# Negative_Pwr.net
KiCad netlist of a schematic drawn in Altium Designer
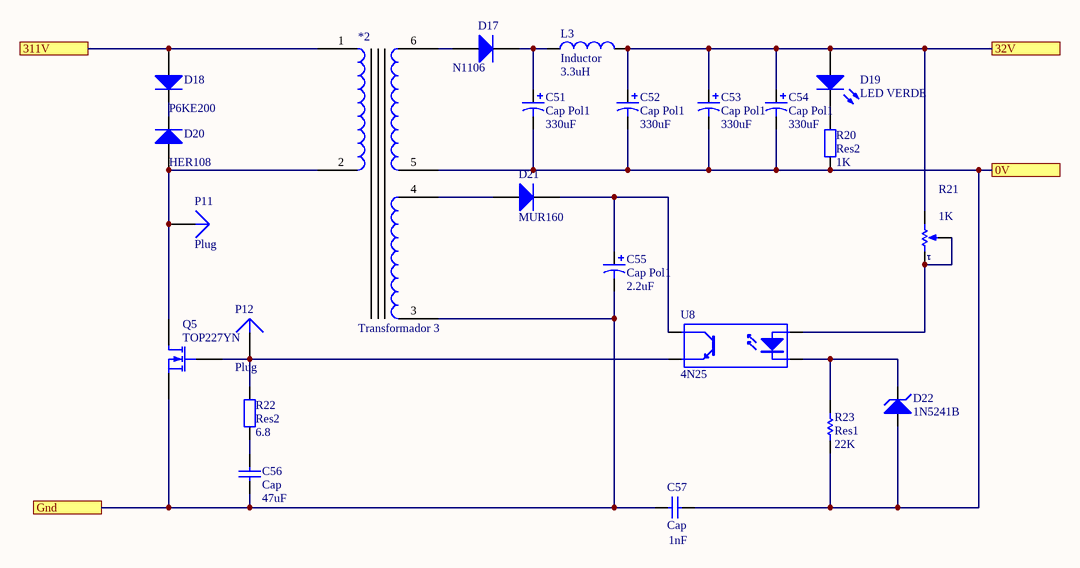
[diagram p0: Negative Pwr.SchDoc]

(export (version "E")
  (design (tool "Eeschema 10.0.6"))
  (components
    (comp (ref "*2")
      (value "Transformador 3")
      (footprint "Transformador_flyback - duplicate")
      (libsource (lib "Userlib") (part "Transformador 3"))
    )
    (comp (ref "C51")
      (value "Cap Pol1")
      (footprint "CAPR D500 H1200 R200 mil")
      (description "Polarized Capacitor (Radial)")
      (fields (field (name "ALTIUM_VALUE") "330uF") (field (name "PUBLISHER") "Altium Limited"))
      (libsource (lib "Miscellaneous Devices") (part "Cap Pol1"))
    )
    (comp (ref "C52")
      (value "Cap Pol1")
      (footprint "CAPR D500 H1200 R200 mil")
      (description "Polarized Capacitor (Radial)")
      (fields (field (name "ALTIUM_VALUE") "330uF") (field (name "PUBLISHER") "Altium Limited"))
      (libsource (lib "Miscellaneous Devices") (part "Cap Pol1"))
    )
    (comp (ref "C53")
      (value "Cap Pol1")
      (footprint "CAPR D500 H1200 R200 mil")
      (description "Polarized Capacitor (Radial)")
      (fields (field (name "ALTIUM_VALUE") "330uF") (field (name "PUBLISHER") "Altium Limited"))
      (libsource (lib "Miscellaneous Devices") (part "Cap Pol1"))
    )
    (comp (ref "C54")
      (value "Cap Pol1")
      (footprint "CAPR D500 H1200 R200 mil")
      (description "Polarized Capacitor (Radial)")
      (fields (field (name "ALTIUM_VALUE") "330uF") (field (name "PUBLISHER") "Altium Limited"))
      (libsource (lib "Miscellaneous Devices") (part "Cap Pol1"))
    )
    (comp (ref "C55")
      (value "Cap Pol1")
      (footprint "CAPR D200 H450 R100 mil")
      (description "Polarized Capacitor (Radial)")
      (fields (field (name "ALTIUM_VALUE") "2.2uF") (field (name "PUBLISHER") "Altium Limited"))
      (libsource (lib "Miscellaneous Devices") (part "Cap Pol1"))
    )
    (comp (ref "C56")
      (value "Cap")
      (footprint "CAPR D250 H450 R100 mil")
      (description "Capacitor")
      (fields (field (name "ALTIUM_VALUE") "47uF") (field (name "PUBLISHER") "Altium Limited"))
      (libsource (lib "Miscellaneous Devices") (part "Cap"))
    )
    (comp (ref "C57")
      (value "Cap")
      (footprint "RAD-0.2")
      (description "Capacitor")
      (fields (field (name "ALTIUM_VALUE") "1nF") (field (name "PUBLISHER") "Altium Limited"))
      (libsource (lib "Miscellaneous Devices") (part "Cap"))
    )
    (comp (ref "D17")
      (value "N1106")
      (footprint "TO-220_A")
      (description "High Conductance Fast Diode")
      (fields (field (name "PUBLISHER") "Altium Limited"))
      (libsource (lib "") (part "Diode 1N4148_1"))
    )
    (comp (ref "D18")
      (value "P6KE200")
      (footprint "DO-15")
      (description "High Conductance Fast Diode")
      (fields (field (name "PUBLISHER") "Altium Limited"))
      (libsource (lib "Miscellaneous Devices") (part "Diode 1N4148"))
    )
    (comp (ref "D19")
      (value "LED VERDE")
      (footprint "Led 5mm ROJO")
      (description "Typical INFRARED GaAs LED")
      (fields (field (name "PUBLISHER") "Altium Limited"))
      (libsource (lib "Miscellaneous Devices") (part "LED0"))
    )
    (comp (ref "D20")
      (value "HER108")
      (footprint "DO-41")
      (description "High Conductance Fast Diode")
      (fields (field (name "PUBLISHER") "Altium Limited"))
      (libsource (lib "Miscellaneous Devices") (part "Diode 1N4148"))
    )
    (comp (ref "D21")
      (value "MUR160")
      (footprint "DO-41")
      (description "High Conductance Fast Diode")
      (fields (field (name "PUBLISHER") "Altium Limited"))
      (libsource (lib "Miscellaneous Devices") (part "Diode 1N4148"))
    )
    (comp (ref "D22")
      (value "Diodo Zener")
      (footprint "DO-41")
      (fields (field (name "VALOR") "1N5241B"))
      (libsource (lib "RUF-Dispositivos-Grales") (part "Diodo Zener"))
    )
    (comp (ref "L3")
      (value "Inductor")
      (footprint "Bobina 1.5*3")
      (fields (field (name "ALTIUM_VALUE") "3.3uH") (field (name "PUBLISHER") "Altium Limited"))
      (libsource (lib "Miscellaneous Devices") (part "Inductor"))
    )
    (comp (ref "P11")
      (value "Plug")
      (footprint "PIN1")
      (fields (field (name "PUBLISHER") "Altium Limited"))
      (libsource (lib "Miscellaneous Connectors") (part "Plug"))
    )
    (comp (ref "P12")
      (value "Plug")
      (footprint "PIN1")
      (fields (field (name "PUBLISHER") "Altium Limited"))
      (libsource (lib "Miscellaneous Connectors") (part "Plug"))
    )
    (comp (ref "Q5")
      (value "TOP227YN")
      (footprint "TO-220AB")
      (description "N-Channel MOSFET")
      (fields (field (name "PUBLISHER") "Altium Limited"))
      (libsource (lib "Miscellaneous Devices") (part "MOSFET-N"))
    )
    (comp (ref "R20")
      (value "Res2")
      (footprint "1206 resistor")
      (description "Resistor")
      (fields (field (name "ALTIUM_VALUE") "1K") (field (name "PUBLISHER") "Altium Limited"))
      (libsource (lib "Miscellaneous Devices") (part "Res2"))
    )
    (comp (ref "R21")
      (value "Trimpot")
      (footprint "Trimpot Horizontal")
      (description "Preset")
      (fields (field (name "VALOR") "1K"))
      (libsource (lib "RUF-Dispositivos-Grales") (part "Trimpot"))
    )
    (comp (ref "R22")
      (value "Res2")
      (footprint "1206 resistor")
      (description "Resistor")
      (fields (field (name "ALTIUM_VALUE") "6.8") (field (name "PUBLISHER") "Altium Limited"))
      (libsource (lib "Miscellaneous Devices") (part "Res2"))
    )
    (comp (ref "R23")
      (value "Res1")
      (footprint "1206 resistor")
      (description "Resistor")
      (fields (field (name "ALTIUM_VALUE") "22K") (field (name "PUBLISHER") "Altium Limited"))
      (libsource (lib "Miscellaneous Devices") (part "Res1"))
    )
    (comp (ref "U8")
      (value "4N25")
      (footprint "DIP-4")
      (description "4-Pin Phototransistor Optocoupler")
      (fields (field (name "PUBLISHER") "Altium Limited"))
      (libsource (lib "Miscellaneous Devices") (part "Optoisolator1"))
    )
  )
  (nets
    (net (code "1") (name "/0V") (class "Default")
      (node (ref "*2") (pin "5") (pinfunction "L_5") (pintype "passive"))
      (node (ref "C51") (pin "2") (pinfunction "2_2") (pintype "passive"))
      (node (ref "C52") (pin "2") (pinfunction "2_2") (pintype "passive"))
      (node (ref "C53") (pin "2") (pinfunction "2_2") (pintype "passive"))
      (node (ref "C54") (pin "2") (pinfunction "2_2") (pintype "passive"))
      (node (ref "C57") (pin "2") (pinfunction "2_2") (pintype "passive"))
      (node (ref "D22") (pin "1") (pinfunction "A_1") (pintype "passive"))
      (node (ref "R20") (pin "1") (pinfunction "1_1") (pintype "passive"))
      (node (ref "R23") (pin "1") (pinfunction "1_1") (pintype "passive"))
    )
    (net (code "2") (name "/32V") (class "Default")
      (node (ref "C52") (pin "1") (pinfunction "1_1") (pintype "passive"))
      (node (ref "C53") (pin "1") (pinfunction "1_1") (pintype "passive"))
      (node (ref "C54") (pin "1") (pinfunction "1_1") (pintype "passive"))
      (node (ref "D19") (pin "1") (pinfunction "A_1") (pintype "passive"))
      (node (ref "L3") (pin "2") (pinfunction "2_2") (pintype "passive"))
      (node (ref "R21") (pin "2") (pinfunction "BOT_2") (pintype "passive"))
    )
    (net (code "3") (name "/311V") (class "Default")
      (node (ref "*2") (pin "1") (pinfunction "L_1") (pintype "passive"))
      (node (ref "D18") (pin "1") (pinfunction "A_1") (pintype "passive"))
    )
    (net (code "4") (name "/Gnd") (class "Default")
      (node (ref "*2") (pin "3") (pinfunction "L_3") (pintype "passive"))
      (node (ref "C55") (pin "2") (pinfunction "2_2") (pintype "passive"))
      (node (ref "C56") (pin "1") (pinfunction "1_1") (pintype "passive"))
      (node (ref "C57") (pin "1") (pinfunction "1_1") (pintype "passive"))
      (node (ref "Q5") (pin "2") (pinfunction "S_2") (pintype "passive"))
    )
    (net (code "5") (name "Net-(C56-Pad2)") (class "Default")
      (node (ref "C56") (pin "2") (pinfunction "2_2") (pintype "passive"))
      (node (ref "R22") (pin "1") (pinfunction "1_1") (pintype "passive"))
    )
    (net (code "6") (name "Net-(D17-A)") (class "Default")
      (node (ref "*2") (pin "6") (pinfunction "L_6") (pintype "passive"))
      (node (ref "D17") (pin "3") (pinfunction "A_3") (pintype "passive"))
    )
    (net (code "7") (name "Net-(D17-K)") (class "Default")
      (node (ref "C51") (pin "1") (pinfunction "1_1") (pintype "passive"))
      (node (ref "D17") (pin "1") (pinfunction "K_1") (pintype "passive"))
      (node (ref "L3") (pin "1") (pinfunction "1_1") (pintype "passive"))
    )
    (net (code "8") (name "Net-(D18-K)") (class "Default")
      (node (ref "D18") (pin "2") (pinfunction "K_2") (pintype "passive"))
      (node (ref "D20") (pin "2") (pinfunction "K_2") (pintype "passive"))
    )
    (net (code "9") (name "Net-(D19-K)") (class "Default")
      (node (ref "D19") (pin "2") (pinfunction "K_2") (pintype "passive"))
      (node (ref "R20") (pin "2") (pinfunction "2_2") (pintype "passive"))
    )
    (net (code "10") (name "Net-(D20-A)") (class "Default")
      (node (ref "*2") (pin "2") (pinfunction "L_2") (pintype "passive"))
      (node (ref "D20") (pin "1") (pinfunction "A_1") (pintype "passive"))
      (node (ref "P11") (pin "1") (pinfunction "1_1") (pintype "passive"))
      (node (ref "Q5") (pin "3") (pinfunction "D_3") (pintype "passive"))
    )
    (net (code "11") (name "Net-(D21-A)") (class "Default")
      (node (ref "*2") (pin "4") (pinfunction "L_4") (pintype "passive"))
      (node (ref "D21") (pin "1") (pinfunction "A_1") (pintype "passive"))
    )
    (net (code "12") (name "Net-(D21-K)") (class "Default")
      (node (ref "C55") (pin "1") (pinfunction "1_1") (pintype "passive"))
      (node (ref "D21") (pin "2") (pinfunction "K_2") (pintype "passive"))
      (node (ref "U8") (pin "4") (pinfunction "C_4") (pintype "passive"))
    )
    (net (code "13") (name "Net-(D22-K)") (class "Default")
      (node (ref "D22") (pin "2") (pinfunction "K_2") (pintype "passive"))
      (node (ref "R23") (pin "2") (pinfunction "2_2") (pintype "passive"))
      (node (ref "U8") (pin "2") (pinfunction "K_2") (pintype "passive"))
    )
    (net (code "14") (name "Net-(Q5-G)") (class "Default")
      (node (ref "P12") (pin "1") (pinfunction "1_1") (pintype "passive"))
      (node (ref "Q5") (pin "1") (pinfunction "G_1") (pintype "passive"))
      (node (ref "R22") (pin "2") (pinfunction "2_2") (pintype "passive"))
      (node (ref "U8") (pin "3") (pinfunction "E_3") (pintype "passive"))
    )
    (net (code "15") (name "Net-(R21-TAP)") (class "Default")
      (node (ref "R21") (pin "1") (pinfunction "TOP_1") (pintype "passive"))
      (node (ref "R21") (pin "3") (pinfunction "TAP_3") (pintype "passive"))
      (node (ref "U8") (pin "1") (pinfunction "A_1") (pintype "passive"))
    )
  )
)
